# 1TTR4---_Cumbo_Fabio_---_LED_Double.net
KiCad netlist of a schematic drawn in EAGLE
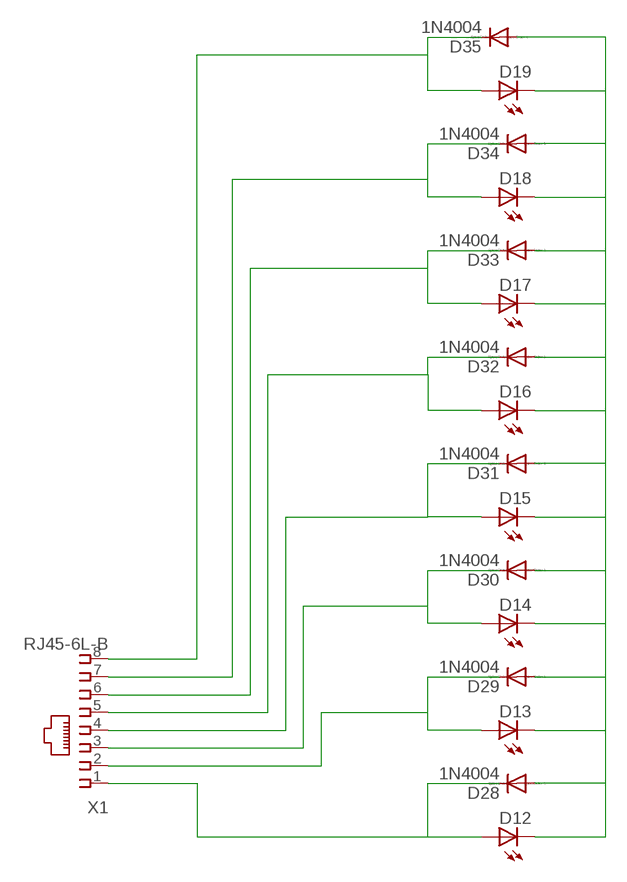
[diagram p0: schematic, sheet 1]

(export (version "E")
  (design (tool "Eeschema 10.0.6"))
  (components
    (comp (ref "D12")
      (value "LED5MM")
      (footprint "eagle-import:LED5MM")
      (libsource (lib "eagle-import") (part "LED5MM"))
    )
    (comp (ref "D13")
      (value "LED5MM")
      (footprint "eagle-import:LED5MM")
      (libsource (lib "eagle-import") (part "LED5MM"))
    )
    (comp (ref "D14")
      (value "LED5MM")
      (footprint "eagle-import:LED5MM")
      (libsource (lib "eagle-import") (part "LED5MM"))
    )
    (comp (ref "D15")
      (value "LED5MM")
      (footprint "eagle-import:LED5MM")
      (libsource (lib "eagle-import") (part "LED5MM"))
    )
    (comp (ref "D16")
      (value "LED5MM")
      (footprint "eagle-import:LED5MM")
      (libsource (lib "eagle-import") (part "LED5MM"))
    )
    (comp (ref "D17")
      (value "LED5MM")
      (footprint "eagle-import:LED5MM")
      (libsource (lib "eagle-import") (part "LED5MM"))
    )
    (comp (ref "D18")
      (value "LED5MM")
      (footprint "eagle-import:LED5MM")
      (libsource (lib "eagle-import") (part "LED5MM"))
    )
    (comp (ref "D19")
      (value "LED5MM")
      (footprint "eagle-import:LED5MM")
      (libsource (lib "eagle-import") (part "LED5MM"))
    )
    (comp (ref "D28")
      (value "1N4004")
      (footprint "eagle-import:DO41-10")
      (libsource (lib "eagle-import") (part "1N4004"))
    )
    (comp (ref "D29")
      (value "1N4004")
      (footprint "eagle-import:DO41-10")
      (libsource (lib "eagle-import") (part "1N4004"))
    )
    (comp (ref "D30")
      (value "1N4004")
      (footprint "eagle-import:DO41-10")
      (libsource (lib "eagle-import") (part "1N4004"))
    )
    (comp (ref "D31")
      (value "1N4004")
      (footprint "eagle-import:DO41-10")
      (libsource (lib "eagle-import") (part "1N4004"))
    )
    (comp (ref "D32")
      (value "1N4004")
      (footprint "eagle-import:DO41-10")
      (libsource (lib "eagle-import") (part "1N4004"))
    )
    (comp (ref "D33")
      (value "1N4004")
      (footprint "eagle-import:DO41-10")
      (libsource (lib "eagle-import") (part "1N4004"))
    )
    (comp (ref "D34")
      (value "1N4004")
      (footprint "eagle-import:DO41-10")
      (libsource (lib "eagle-import") (part "1N4004"))
    )
    (comp (ref "D35")
      (value "1N4004")
      (footprint "eagle-import:DO41-10")
      (libsource (lib "eagle-import") (part "1N4004"))
    )
    (comp (ref "X1")
      (value "RJ45-6L-B")
      (footprint "eagle-import:RJ45-NO-SHIELD")
      (libsource (lib "eagle-import") (part "RJ45-6L-B"))
    )
  )
  (nets
    (net (code "1") (name "Net-(D12-C)") (class "Default")
      (node (ref "D12") (pin "K") (pinfunction "C_K") (pintype "passive"))
      (node (ref "D13") (pin "K") (pinfunction "C_K") (pintype "passive"))
      (node (ref "D14") (pin "K") (pinfunction "C_K") (pintype "passive"))
      (node (ref "D15") (pin "K") (pinfunction "C_K") (pintype "passive"))
      (node (ref "D16") (pin "K") (pinfunction "C_K") (pintype "passive"))
      (node (ref "D17") (pin "K") (pinfunction "C_K") (pintype "passive"))
      (node (ref "D18") (pin "K") (pinfunction "C_K") (pintype "passive"))
      (node (ref "D19") (pin "K") (pinfunction "C_K") (pintype "passive"))
      (node (ref "D28") (pin "A") (pinfunction "A_A") (pintype "passive"))
      (node (ref "D29") (pin "A") (pinfunction "A_A") (pintype "passive"))
      (node (ref "D30") (pin "A") (pinfunction "A_A") (pintype "passive"))
      (node (ref "D31") (pin "A") (pinfunction "A_A") (pintype "passive"))
      (node (ref "D32") (pin "A") (pinfunction "A_A") (pintype "passive"))
      (node (ref "D33") (pin "A") (pinfunction "A_A") (pintype "passive"))
      (node (ref "D34") (pin "A") (pinfunction "A_A") (pintype "passive"))
      (node (ref "D35") (pin "A") (pinfunction "A_A") (pintype "passive"))
    )
    (net (code "2") (name "Net-(D12-PadA)") (class "Default")
      (node (ref "D12") (pin "A") (pinfunction "A_A") (pintype "passive"))
      (node (ref "D28") (pin "C") (pinfunction "C_C") (pintype "passive"))
      (node (ref "X1") (pin "1") (pinfunction "1_1") (pintype "passive"))
    )
    (net (code "3") (name "Net-(D13-PadA)") (class "Default")
      (node (ref "D13") (pin "A") (pinfunction "A_A") (pintype "passive"))
      (node (ref "D29") (pin "C") (pinfunction "C_C") (pintype "passive"))
      (node (ref "X1") (pin "2") (pinfunction "2_2") (pintype "passive"))
    )
    (net (code "4") (name "Net-(D14-PadA)") (class "Default")
      (node (ref "D14") (pin "A") (pinfunction "A_A") (pintype "passive"))
      (node (ref "D30") (pin "C") (pinfunction "C_C") (pintype "passive"))
      (node (ref "X1") (pin "3") (pinfunction "3_3") (pintype "passive"))
    )
    (net (code "5") (name "Net-(D15-PadA)") (class "Default")
      (node (ref "D15") (pin "A") (pinfunction "A_A") (pintype "passive"))
      (node (ref "D31") (pin "C") (pinfunction "C_C") (pintype "passive"))
      (node (ref "X1") (pin "4") (pinfunction "4_4") (pintype "passive"))
    )
    (net (code "6") (name "Net-(D16-PadA)") (class "Default")
      (node (ref "D16") (pin "A") (pinfunction "A_A") (pintype "passive"))
      (node (ref "D32") (pin "C") (pinfunction "C_C") (pintype "passive"))
      (node (ref "X1") (pin "5") (pinfunction "5_5") (pintype "passive"))
    )
    (net (code "7") (name "Net-(D17-PadA)") (class "Default")
      (node (ref "D17") (pin "A") (pinfunction "A_A") (pintype "passive"))
      (node (ref "D33") (pin "C") (pinfunction "C_C") (pintype "passive"))
      (node (ref "X1") (pin "6") (pinfunction "6_6") (pintype "passive"))
    )
    (net (code "8") (name "Net-(D18-PadA)") (class "Default")
      (node (ref "D18") (pin "A") (pinfunction "A_A") (pintype "passive"))
      (node (ref "D34") (pin "C") (pinfunction "C_C") (pintype "passive"))
      (node (ref "X1") (pin "7") (pinfunction "7_7") (pintype "passive"))
    )
    (net (code "9") (name "Net-(D19-PadA)") (class "Default")
      (node (ref "D19") (pin "A") (pinfunction "A_A") (pintype "passive"))
      (node (ref "D35") (pin "C") (pinfunction "C_C") (pintype "passive"))
      (node (ref "X1") (pin "8") (pinfunction "8_8") (pintype "passive"))
    )
  )
)
